# mechanism-brd.net
KiCad netlist of a schematic drawn in EAGLE
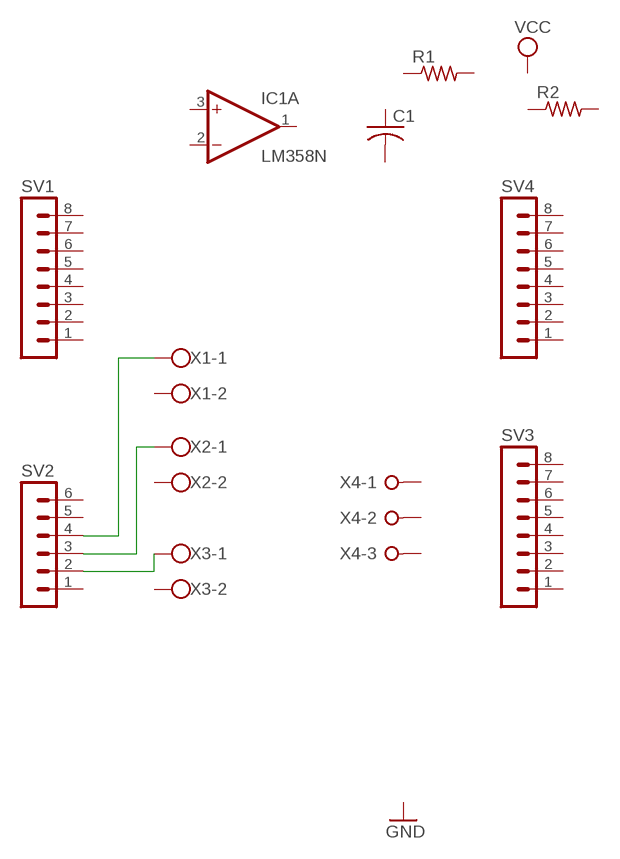
[diagram p0: schematic, sheet 1]

(export (version "E")
  (design (tool "Eeschema 10.0.6"))
  (components
    (comp (ref "C1")
      (value "C-US025-024X044")
      (footprint "eagle-import:C025-024X044")
      (libsource (lib "eagle-import") (part "C-US025-024X044"))
    )
    (comp (ref "IC1")
      (value "LM358N")
      (footprint "eagle-import:DIL08")
      (libsource (lib "eagle-import") (part "LM358N"))
    )
    (comp (ref "R1")
      (value "R-US_0204/5")
      (footprint "eagle-import:0204_5")
      (libsource (lib "eagle-import") (part "R-US_0204/5"))
    )
    (comp (ref "R2")
      (value "R-US_0204/5")
      (footprint "eagle-import:0204_5")
      (libsource (lib "eagle-import") (part "R-US_0204/5"))
    )
    (comp (ref "SV1")
      (value "MA08-1")
      (footprint "eagle-import:MA08-1")
      (libsource (lib "eagle-import") (part "MA08-1"))
    )
    (comp (ref "SV2")
      (value "MA06-1")
      (footprint "eagle-import:MA06-1")
      (libsource (lib "eagle-import") (part "MA06-1"))
    )
    (comp (ref "SV3")
      (value "MA08-1")
      (footprint "eagle-import:MA08-1")
      (libsource (lib "eagle-import") (part "MA08-1"))
    )
    (comp (ref "SV4")
      (value "MA08-1")
      (footprint "eagle-import:MA08-1")
      (libsource (lib "eagle-import") (part "MA08-1"))
    )
    (comp (ref "X1")
      (value "W237-102")
      (footprint "eagle-import:W237-102")
      (fields (field (name "MPN") "237-102"))
      (libsource (lib "eagle-import") (part "W237-102"))
    )
    (comp (ref "X2")
      (value "W237-102")
      (footprint "eagle-import:W237-102")
      (fields (field (name "MPN") "237-102"))
      (libsource (lib "eagle-import") (part "W237-102"))
    )
    (comp (ref "X3")
      (value "W237-102")
      (footprint "eagle-import:W237-102")
      (fields (field (name "MPN") "237-102"))
      (libsource (lib "eagle-import") (part "W237-102"))
    )
    (comp (ref "X4")
      (value "W237-3E")
      (footprint "eagle-import:W237-3E")
      (libsource (lib "eagle-import") (part "W237-3E"))
    )
  )
  (nets
    (net (code "2") (name "Net-(X1A-KL)") (class "Default")
      (node (ref "SV2") (pin "4") (pinfunction "4_4") (pintype "passive"))
      (node (ref "X1") (pin "1") (pinfunction "KL_1") (pintype "passive"))
    )
    (net (code "3") (name "Net-(X2A-KL)") (class "Default")
      (node (ref "SV2") (pin "3") (pinfunction "3_3") (pintype "passive"))
      (node (ref "X2") (pin "1") (pinfunction "KL_1") (pintype "passive"))
    )
    (net (code "4") (name "Net-(X3A-KL)") (class "Default")
      (node (ref "SV2") (pin "2") (pinfunction "2_2") (pintype "passive"))
      (node (ref "X3") (pin "1") (pinfunction "KL_1") (pintype "passive"))
    )
    (net (code "6") (name "unconnected-(C1-Pad1)") (class "Default")
      (node (ref "C1") (pin "1") (pinfunction "1_1") (pintype "passive"))
    )
    (net (code "7") (name "unconnected-(C1-Pad2)") (class "Default")
      (node (ref "C1") (pin "2") (pinfunction "2_2") (pintype "passive"))
    )
    (net (code "8") (name "unconnected-(IC1A-+IN-Pad3)") (class "Default")
      (node (ref "IC1") (pin "3") (pinfunction "+IN_3") (pintype "input"))
    )
    (net (code "9") (name "unconnected-(IC1A--IN-Pad2)") (class "Default")
      (node (ref "IC1") (pin "2") (pinfunction "-IN_2") (pintype "input"))
    )
    (net (code "10") (name "unconnected-(IC1A-OUT-Pad1)") (class "Default")
      (node (ref "IC1") (pin "1") (pinfunction "OUT_1") (pintype "output"))
    )
    (net (code "11") (name "unconnected-(R1-Pad1)") (class "Default")
      (node (ref "R1") (pin "1") (pinfunction "1_1") (pintype "passive"))
    )
    (net (code "12") (name "unconnected-(R1-Pad2)") (class "Default")
      (node (ref "R1") (pin "2") (pinfunction "2_2") (pintype "passive"))
    )
    (net (code "13") (name "unconnected-(R2-Pad1)") (class "Default")
      (node (ref "R2") (pin "1") (pinfunction "1_1") (pintype "passive"))
    )
    (net (code "14") (name "unconnected-(R2-Pad2)") (class "Default")
      (node (ref "R2") (pin "2") (pinfunction "2_2") (pintype "passive"))
    )
    (net (code "15") (name "unconnected-(SV1-Pad1)") (class "Default")
      (node (ref "SV1") (pin "1") (pinfunction "1_1") (pintype "passive"))
    )
    (net (code "16") (name "unconnected-(SV1-Pad2)") (class "Default")
      (node (ref "SV1") (pin "2") (pinfunction "2_2") (pintype "passive"))
    )
    (net (code "17") (name "unconnected-(SV1-Pad3)") (class "Default")
      (node (ref "SV1") (pin "3") (pinfunction "3_3") (pintype "passive"))
    )
    (net (code "18") (name "unconnected-(SV1-Pad4)") (class "Default")
      (node (ref "SV1") (pin "4") (pinfunction "4_4") (pintype "passive"))
    )
    (net (code "19") (name "unconnected-(SV1-Pad5)") (class "Default")
      (node (ref "SV1") (pin "5") (pinfunction "5_5") (pintype "passive"))
    )
    (net (code "20") (name "unconnected-(SV1-Pad6)") (class "Default")
      (node (ref "SV1") (pin "6") (pinfunction "6_6") (pintype "passive"))
    )
    (net (code "21") (name "unconnected-(SV1-Pad7)") (class "Default")
      (node (ref "SV1") (pin "7") (pinfunction "7_7") (pintype "passive"))
    )
    (net (code "22") (name "unconnected-(SV1-Pad8)") (class "Default")
      (node (ref "SV1") (pin "8") (pinfunction "8_8") (pintype "passive"))
    )
    (net (code "23") (name "unconnected-(SV2-Pad1)") (class "Default")
      (node (ref "SV2") (pin "1") (pinfunction "1_1") (pintype "passive"))
    )
    (net (code "24") (name "unconnected-(SV2-Pad5)") (class "Default")
      (node (ref "SV2") (pin "5") (pinfunction "5_5") (pintype "passive"))
    )
    (net (code "25") (name "unconnected-(SV2-Pad6)") (class "Default")
      (node (ref "SV2") (pin "6") (pinfunction "6_6") (pintype "passive"))
    )
    (net (code "26") (name "unconnected-(SV3-Pad1)") (class "Default")
      (node (ref "SV3") (pin "1") (pinfunction "1_1") (pintype "passive"))
    )
    (net (code "27") (name "unconnected-(SV3-Pad2)") (class "Default")
      (node (ref "SV3") (pin "2") (pinfunction "2_2") (pintype "passive"))
    )
    (net (code "28") (name "unconnected-(SV3-Pad3)") (class "Default")
      (node (ref "SV3") (pin "3") (pinfunction "3_3") (pintype "passive"))
    )
    (net (code "29") (name "unconnected-(SV3-Pad4)") (class "Default")
      (node (ref "SV3") (pin "4") (pinfunction "4_4") (pintype "passive"))
    )
    (net (code "30") (name "unconnected-(SV3-Pad5)") (class "Default")
      (node (ref "SV3") (pin "5") (pinfunction "5_5") (pintype "passive"))
    )
    (net (code "31") (name "unconnected-(SV3-Pad6)") (class "Default")
      (node (ref "SV3") (pin "6") (pinfunction "6_6") (pintype "passive"))
    )
    (net (code "32") (name "unconnected-(SV3-Pad7)") (class "Default")
      (node (ref "SV3") (pin "7") (pinfunction "7_7") (pintype "passive"))
    )
    (net (code "33") (name "unconnected-(SV3-Pad8)") (class "Default")
      (node (ref "SV3") (pin "8") (pinfunction "8_8") (pintype "passive"))
    )
    (net (code "34") (name "unconnected-(SV4-Pad1)") (class "Default")
      (node (ref "SV4") (pin "1") (pinfunction "1_1") (pintype "passive"))
    )
    (net (code "35") (name "unconnected-(SV4-Pad2)") (class "Default")
      (node (ref "SV4") (pin "2") (pinfunction "2_2") (pintype "passive"))
    )
    (net (code "36") (name "unconnected-(SV4-Pad3)") (class "Default")
      (node (ref "SV4") (pin "3") (pinfunction "3_3") (pintype "passive"))
    )
    (net (code "37") (name "unconnected-(SV4-Pad4)") (class "Default")
      (node (ref "SV4") (pin "4") (pinfunction "4_4") (pintype "passive"))
    )
    (net (code "38") (name "unconnected-(SV4-Pad5)") (class "Default")
      (node (ref "SV4") (pin "5") (pinfunction "5_5") (pintype "passive"))
    )
    (net (code "39") (name "unconnected-(SV4-Pad6)") (class "Default")
      (node (ref "SV4") (pin "6") (pinfunction "6_6") (pintype "passive"))
    )
    (net (code "40") (name "unconnected-(SV4-Pad7)") (class "Default")
      (node (ref "SV4") (pin "7") (pinfunction "7_7") (pintype "passive"))
    )
    (net (code "41") (name "unconnected-(SV4-Pad8)") (class "Default")
      (node (ref "SV4") (pin "8") (pinfunction "8_8") (pintype "passive"))
    )
    (net (code "42") (name "unconnected-(X1B-KL-Pad2)") (class "Default")
      (node (ref "X1") (pin "2") (pinfunction "KL_2") (pintype "passive"))
    )
    (net (code "43") (name "unconnected-(X2B-KL-Pad2)") (class "Default")
      (node (ref "X2") (pin "2") (pinfunction "KL_2") (pintype "passive"))
    )
    (net (code "44") (name "unconnected-(X3B-KL-Pad2)") (class "Default")
      (node (ref "X3") (pin "2") (pinfunction "KL_2") (pintype "passive"))
    )
    (net (code "45") (name "unconnected-(X4A-KL-Pad1)") (class "Default")
      (node (ref "X4") (pin "1") (pinfunction "KL_1") (pintype "passive"))
    )
    (net (code "46") (name "unconnected-(X4B-KL-Pad2)") (class "Default")
      (node (ref "X4") (pin "2") (pinfunction "KL_2") (pintype "passive"))
    )
    (net (code "47") (name "unconnected-(X4C-KL-Pad3)") (class "Default")
      (node (ref "X4") (pin "3") (pinfunction "KL_3") (pintype "passive"))
    )
  )
)
